# SimonDuino.net
KiCad netlist of a schematic drawn in Altium Designer
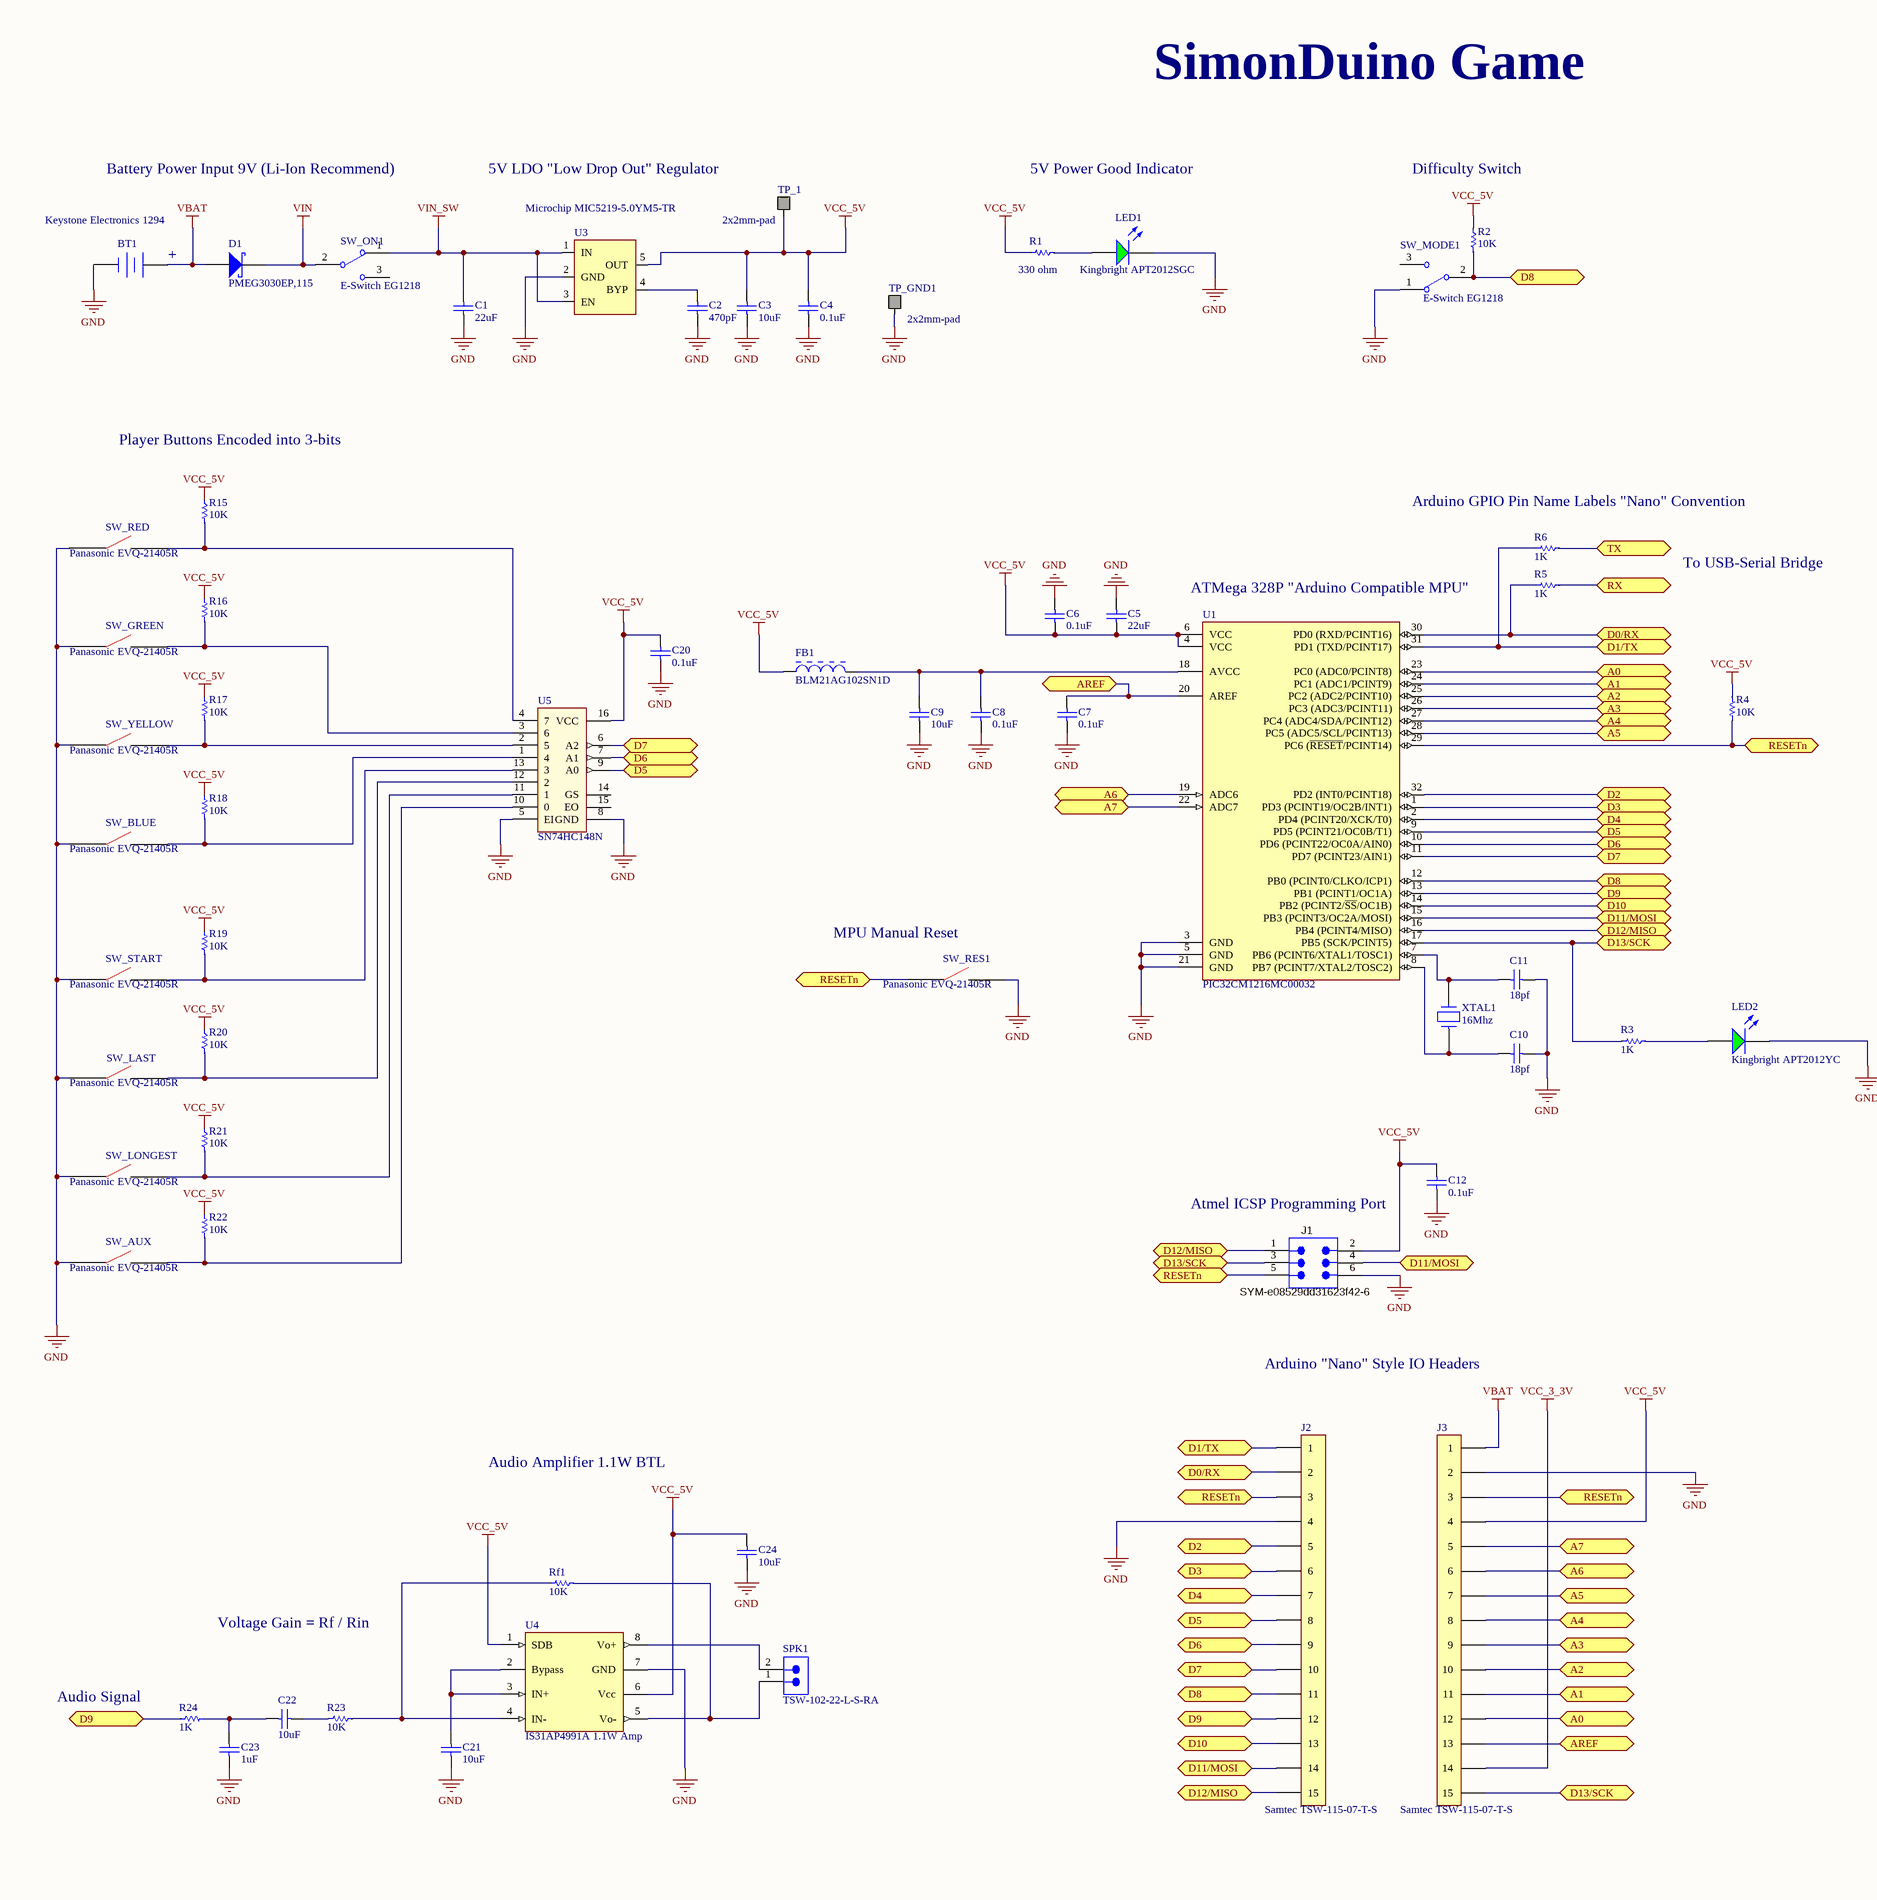
[diagram p0: SimonDuino.SchDoc, left]
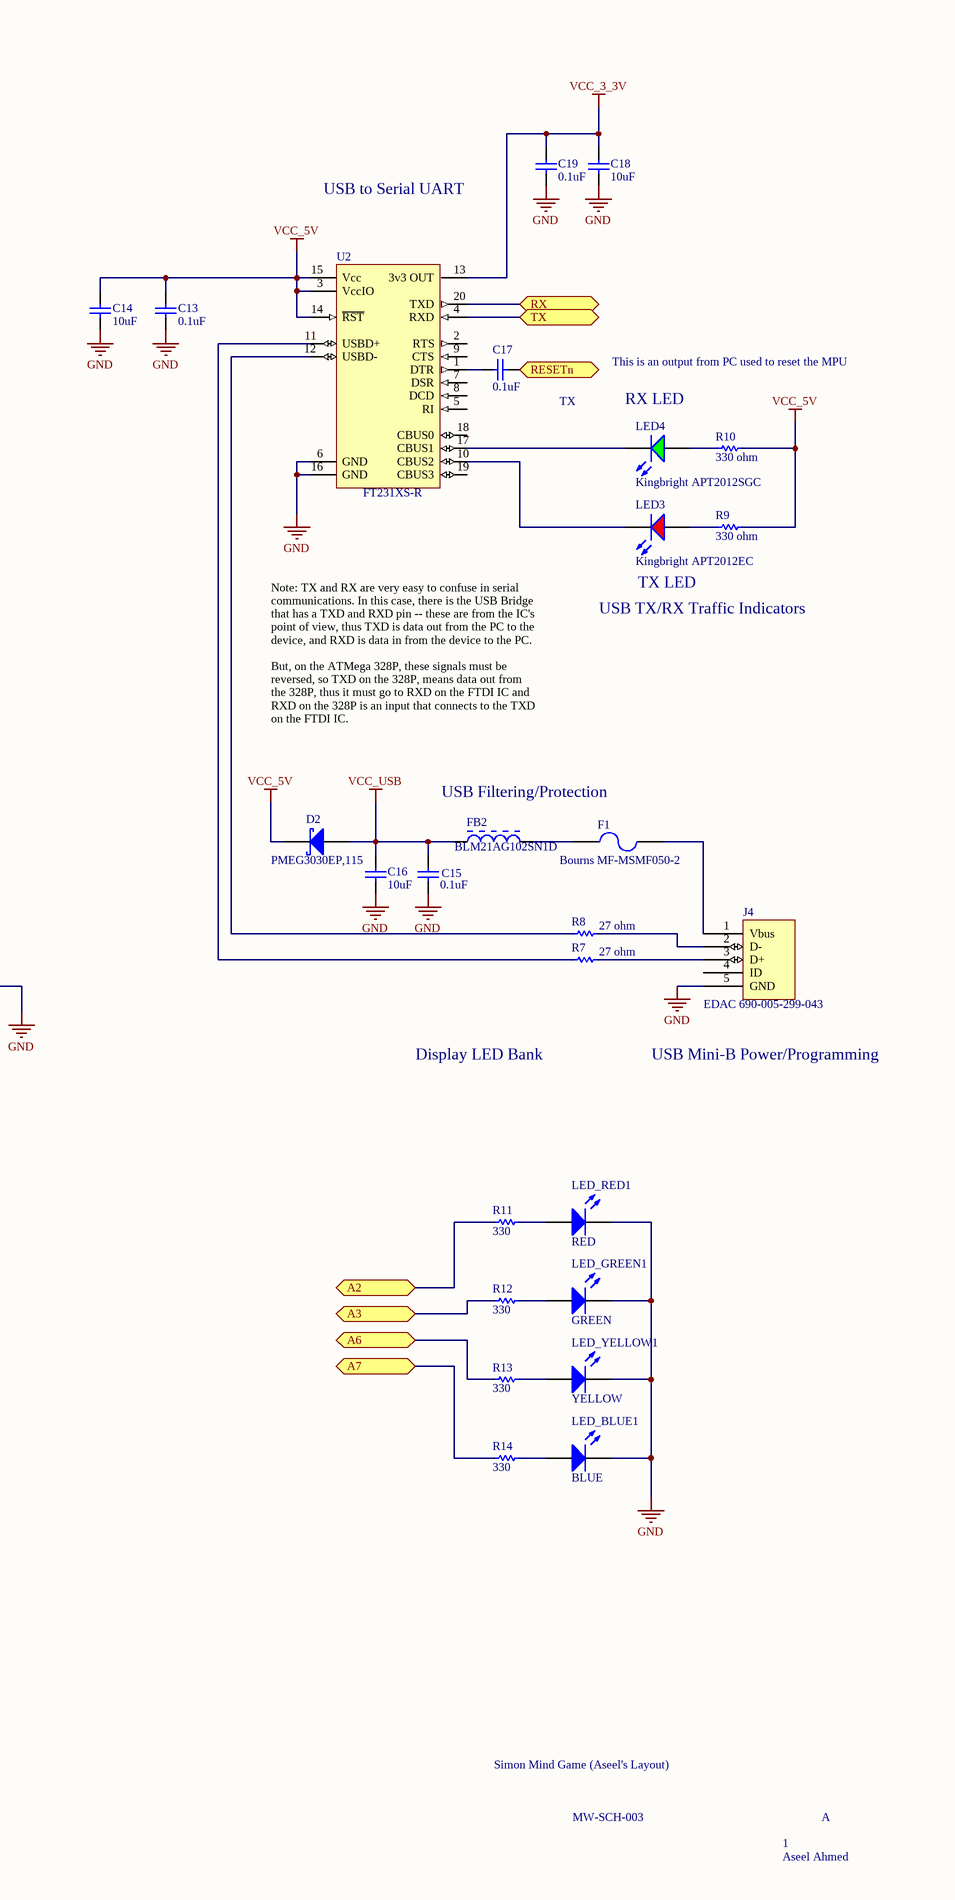
[diagram p1: SimonDuino.SchDoc, right]

(export (version "E")
  (design (tool "Eeschema 10.0.6"))
  (components
    (comp (ref "BT1")
      (value "Keystone Electronics 1294")
      (footprint "PCB-3798-1")
      (description "HOLDER BATT 9V UNIV PLASTIC PC")
      (libsource (lib "Octopart library") (part "SYM-3798-1"))
    )
    (comp (ref "C1")
      (value "22uF")
      (footprint "RLP133A")
      (description "Generic Multilayer Ceramic Capacitor SMD 0805 (2012)")
      (libsource (lib "Octopart library") (part "SYM-3c98f6df3913e35f-5"))
    )
    (comp (ref "C2")
      (value "470pF")
      (footprint "RLP133A")
      (description "Generic Multilayer Ceramic Capacitor SMD 0805 (2012)")
      (libsource (lib "CommunityVault") (part "SYM-3c98f6df3913e35f-5"))
    )
    (comp (ref "C3")
      (value "10uF")
      (footprint "RLP133A")
      (description "Generic Multilayer Ceramic Capacitor SMD 0805 (2012)")
      (libsource (lib "Octopart library") (part "SYM-3c98f6df3913e35f-5"))
    )
    (comp (ref "C4")
      (value "0.1uF")
      (footprint "RLP133A")
      (description "Generic Multilayer Ceramic Capacitor SMD 0805 (2012)")
      (libsource (lib "Octopart library") (part "SYM-3c98f6df3913e35f-5"))
    )
    (comp (ref "C5")
      (value "22uF")
      (footprint "RLP133A")
      (description "Generic Multilayer Ceramic Capacitor SMD 0805 (2012)")
      (libsource (lib "Octopart library") (part "SYM-3c98f6df3913e35f-5"))
    )
    (comp (ref "C6")
      (value "0.1uF")
      (footprint "RLP133A")
      (description "Generic Multilayer Ceramic Capacitor SMD 0805 (2012)")
      (libsource (lib "Octopart library") (part "SYM-3c98f6df3913e35f-5"))
    )
    (comp (ref "C7")
      (value "0.1uF")
      (footprint "RLP133A")
      (description "Generic Multilayer Ceramic Capacitor SMD 0805 (2012)")
      (libsource (lib "Octopart library") (part "SYM-3c98f6df3913e35f-5"))
    )
    (comp (ref "C8")
      (value "0.1uF")
      (footprint "RLP133A")
      (description "Generic Multilayer Ceramic Capacitor SMD 0805 (2012)")
      (libsource (lib "Octopart library") (part "SYM-3c98f6df3913e35f-5"))
    )
    (comp (ref "C9")
      (value "10uF")
      (footprint "RLP133A")
      (description "Generic Multilayer Ceramic Capacitor SMD 0805 (2012)")
      (libsource (lib "Octopart library") (part "SYM-3c98f6df3913e35f-5"))
    )
    (comp (ref "C10")
      (value "18pf")
      (footprint "RLP133A")
      (description "Generic Multilayer Ceramic Capacitor SMD 0805 (2012)")
      (libsource (lib "Octopart library") (part "SYM-3c98f6df3913e35f-5"))
    )
    (comp (ref "C11")
      (value "18pf")
      (footprint "RLP133A")
      (description "Generic Multilayer Ceramic Capacitor SMD 0805 (2012)")
      (libsource (lib "Octopart library") (part "SYM-3c98f6df3913e35f-5"))
    )
    (comp (ref "C12")
      (value "0.1uF")
      (footprint "RLP133A")
      (description "Generic Multilayer Ceramic Capacitor SMD 0805 (2012)")
      (libsource (lib "Octopart library") (part "SYM-3c98f6df3913e35f-5"))
    )
    (comp (ref "C13")
      (value "0.1uF")
      (footprint "RLP133A")
      (description "Generic Multilayer Ceramic Capacitor SMD 0805 (2012)")
      (libsource (lib "Octopart library") (part "SYM-3c98f6df3913e35f-5"))
    )
    (comp (ref "C14")
      (value "10uF")
      (footprint "RLP133A")
      (description "Generic Multilayer Ceramic Capacitor SMD 0805 (2012)")
      (libsource (lib "Octopart library") (part "SYM-3c98f6df3913e35f-5"))
    )
    (comp (ref "C15")
      (value "0.1uF")
      (footprint "RLP133A")
      (description "Generic Multilayer Ceramic Capacitor SMD 0805 (2012)")
      (libsource (lib "Octopart library") (part "SYM-3c98f6df3913e35f-5"))
    )
    (comp (ref "C16")
      (value "10uF")
      (footprint "RLP133A")
      (description "Generic Multilayer Ceramic Capacitor SMD 0805 (2012)")
      (libsource (lib "Octopart library") (part "SYM-3c98f6df3913e35f-5"))
    )
    (comp (ref "C17")
      (value "0.1uF")
      (footprint "RLP133A")
      (description "Generic Multilayer Ceramic Capacitor SMD 0805 (2012)")
      (libsource (lib "Octopart library") (part "SYM-3c98f6df3913e35f-5"))
    )
    (comp (ref "C18")
      (value "10uF")
      (footprint "RLP133A")
      (description "Generic Multilayer Ceramic Capacitor SMD 0805 (2012)")
      (libsource (lib "Octopart library") (part "SYM-3c98f6df3913e35f-5"))
    )
    (comp (ref "C19")
      (value "0.1uF")
      (footprint "RLP133A")
      (description "Generic Multilayer Ceramic Capacitor SMD 0805 (2012)")
      (libsource (lib "Octopart library") (part "SYM-3c98f6df3913e35f-5"))
    )
    (comp (ref "C20")
      (value "0.1uF")
      (footprint "RLP133A")
      (description "Generic Multilayer Ceramic Capacitor SMD 0805 (2012)")
      (libsource (lib "Octopart library") (part "SYM-3c98f6df3913e35f-5"))
    )
    (comp (ref "C21")
      (value "10uF")
      (footprint "RLP133A")
      (description "Generic Multilayer Ceramic Capacitor SMD 0805 (2012)")
      (libsource (lib "Octopart library") (part "SYM-3c98f6df3913e35f-5"))
    )
    (comp (ref "C22")
      (value "10uF")
      (footprint "RLP133A")
      (description "Generic Multilayer Ceramic Capacitor SMD 0805 (2012)")
      (libsource (lib "Octopart library") (part "SYM-3c98f6df3913e35f-5"))
    )
    (comp (ref "C23")
      (value "1uF")
      (footprint "RLP133A")
      (description "Generic Multilayer Ceramic Capacitor SMD 0805 (2012)")
      (libsource (lib "Octopart library") (part "SYM-3c98f6df3913e35f-5"))
    )
    (comp (ref "C24")
      (value "10uF")
      (footprint "RLP133A")
      (description "Generic Multilayer Ceramic Capacitor SMD 0805 (2012)")
      (libsource (lib "Octopart library") (part "SYM-3c98f6df3913e35f-5"))
    )
    (comp (ref "D1")
      (value "PMEG3030EP,115")
      (footprint "PCB-ylvpw7uho1dkst7hexks-1")
      (description "PMEG3030EP 3 A 30 Vrrm SMT MEGA Schottky Barrier Rectifier - SOD-128F")
      (libsource (lib "Octopart library") (part "SYM-93505b4aaf424c97-1"))
    )
    (comp (ref "D2")
      (value "PMEG3030EP,115")
      (footprint "PCB-ylvpw7uho1dkst7hexks-1")
      (description "PMEG3030EP 3 A 30 Vrrm SMT MEGA Schottky Barrier Rectifier - SOD-128F")
      (libsource (lib "Octopart library") (part "SYM-93505b4aaf424c97-1"))
    )
    (comp (ref "F1")
      (value "Bourns MF-MSMF050-2")
      (footprint "L1812")
      (description "PTC RESETTABLE .50A 15V 1812")
      (libsource (lib "Octopart library") (part "BOUR-MF-MSMF050-2"))
    )
    (comp (ref "FB1")
      (value "BLM21AG102SN1D")
      (footprint "MURA-BLM21-H1-CHIP-2_V")
      (libsource (lib "Octopart library") (part "MURA-FB-2"))
    )
    (comp (ref "FB2")
      (value "BLM21AG102SN1D")
      (footprint "MURA-BLM21-H1-CHIP-2_V")
      (libsource (lib "Octopart library") (part "MURA-FB-2"))
    )
    (comp (ref "J1")
      (value "SYM-e08529dd31623f42-6")
      (footprint "PCB-2h1t0rpz2tx2wsc79kkt-1")
      (description "2.54mm (0.1\") Pitch DIL Vertical PC Tail Pin Header, 6.1mm mating pin height, tin, 3+3 contacts")
      (fields (field (name "MANUFACTURER PART NUMBER") "M20-9980346"))
      (libsource (lib "Octopart library") (part "SYM-e08529dd31623f42-6"))
    )
    (comp (ref "J2")
      (value "Samtec TSW-115-07-T-S")
      (footprint "PCB-ss9uik38su1ryg1jck95-1")
      (description "Conn Unshrouded Header HDR 15 POS 2.54mm Solder ST Thru-Hole Automotive Bulk")
      (libsource (lib "") (part "SYM-3393fa9d3e8bec54-1_1"))
    )
    (comp (ref "J3")
      (value "Samtec TSW-115-07-T-S")
      (footprint "PCB-ss9uik38su1ryg1jck95-1")
      (description "Conn Unshrouded Header HDR 15 POS 2.54mm Solder ST Thru-Hole Automotive Bulk")
      (libsource (lib "Octopart library") (part "SYM-3393fa9d3e8bec54-1"))
    )
    (comp (ref "J4")
      (value "EDAC 690-005-299-043")
      (footprint "PCB-0dqtvzwtjwndkeioqta0-1")
      (description "5 Pin Right Angle Surface Mount Mini USB Type B")
      (libsource (lib "CommunityVault") (part "SYM-f10139da97e32ec6-1"))
    )
    (comp (ref "LED1")
      (value "Kingbright APT2012SGC")
      (footprint "CHIPLED_0805_NOOUTLINE")
      (description "LED 2X1.2MM 568NM GN WTR CLR SMD")
      (libsource (lib "Octopart library") (part "LED_GREEN_AC"))
    )
    (comp (ref "LED2")
      (value "Kingbright APT2012YC")
      (footprint "CHIPLED_0805_NOOUTLINE")
      (description "LED 2X1.2MM 568NM GN WTR CLR SMD")
      (libsource (lib "CommunityVault") (part "CMP-1546221-2"))
    )
    (comp (ref "LED3")
      (value "Kingbright APT2012EC")
      (footprint "CHIPLED_0805_NOOUTLINE")
      (description "LED 2X1.2MM 625NM RD WTR CLR SMD")
      (libsource (lib "Octopart library") (part "LED_RED_AC"))
    )
    (comp (ref "LED4")
      (value "Kingbright APT2012SGC")
      (footprint "CHIPLED_0805_NOOUTLINE")
      (description "LED 2X1.2MM 568NM GN WTR CLR SMD")
      (libsource (lib "Octopart library") (part "LED_GREEN_AC"))
    )
    (comp (ref "LED_BLUE1")
      (value "BLUE")
      (footprint "PCB-teu6t62n2bsx7jl1if62-1")
      (description "LED Uni-Color Green 2-Pin T-1 3/4 Bulk")
      (fields
        (field (name "MANUFACTURER PART NUMBER") "C503B-GCN-CY0C0791")
        (field (name "MANUFACTURER") "Cree")
      )
      (libsource (lib "FavoritesLibrary") (part "SYM-92bb5b2eff764d7c-1"))
    )
    (comp (ref "LED_GREEN1")
      (value "GREEN")
      (footprint "PCB-teu6t62n2bsx7jl1if62-1")
      (description "LED Uni-Color Green 2-Pin T-1 3/4 Bulk")
      (fields
        (field (name "MANUFACTURER PART NUMBER") "C503B-GCN-CY0C0791")
        (field (name "MANUFACTURER") "Cree")
      )
      (libsource (lib "FavoritesLibrary") (part "SYM-92bb5b2eff764d7c-1"))
    )
    (comp (ref "LED_RED1")
      (value "RED")
      (footprint "PCB-teu6t62n2bsx7jl1if62-1")
      (description "LED Uni-Color Green 2-Pin T-1 3/4 Bulk")
      (fields
        (field (name "MANUFACTURER PART NUMBER") "C503B-GCN-CY0C0791")
        (field (name "MANUFACTURER") "Cree")
      )
      (libsource (lib "FavoritesLibrary") (part "SYM-92bb5b2eff764d7c-1"))
    )
    (comp (ref "LED_YELLOW1")
      (value "YELLOW")
      (footprint "PCB-teu6t62n2bsx7jl1if62-1")
      (description "LED Uni-Color Green 2-Pin T-1 3/4 Bulk")
      (fields
        (field (name "MANUFACTURER PART NUMBER") "C503B-GCN-CY0C0791")
        (field (name "MANUFACTURER") "Cree")
      )
      (libsource (lib "FavoritesLibrary") (part "SYM-92bb5b2eff764d7c-1"))
    )
    (comp (ref "R1")
      (value "330 ohm")
      (footprint "RESC2013X70X40LL20T20")
      (description "@ RESISTOR,SMT,0805,1K OHM, +/-1%,+-100ppm,THICKFILM(100)")
      (libsource (lib "Octopart library") (part "RES-2"))
    )
    (comp (ref "R2")
      (value "10K")
      (footprint "RESC2013X70X40LL20T20")
      (description "@ RESISTOR,SMT,0805,1K OHM, +/-1%,+-100ppm,THICKFILM(100)")
      (libsource (lib "Octopart library") (part "RES-2"))
    )
    (comp (ref "R3")
      (value "1K")
      (footprint "RESC2013X70X40LL20T20")
      (description "@ RESISTOR,SMT,0805,1K OHM, +/-1%,+-100ppm,THICKFILM(100)")
      (libsource (lib "Octopart library") (part "RES-2"))
    )
    (comp (ref "R4")
      (value "10K")
      (footprint "RESC2013X70X40LL20T20")
      (description "@ RESISTOR,SMT,0805,1K OHM, +/-1%,+-100ppm,THICKFILM(100)")
      (libsource (lib "Octopart library") (part "RES-2"))
    )
    (comp (ref "R5")
      (value "1K")
      (footprint "RESC2013X70X40LL20T20")
      (description "@ RESISTOR,SMT,0805,1K OHM, +/-1%,+-100ppm,THICKFILM(100)")
      (libsource (lib "Octopart library") (part "RES-2"))
    )
    (comp (ref "R6")
      (value "1K")
      (footprint "RESC2013X70X40LL20T20")
      (description "@ RESISTOR,SMT,0805,1K OHM, +/-1%,+-100ppm,THICKFILM(100)")
      (libsource (lib "Octopart library") (part "RES-2"))
    )
    (comp (ref "R7")
      (value "27 ohm")
      (footprint "RESC2013X70X40LL20T20")
      (description "@ RESISTOR,SMT,0805,1K OHM, +/-1%,+-100ppm,THICKFILM(100)")
      (libsource (lib "Octopart library") (part "RES-2"))
    )
    (comp (ref "R8")
      (value "27 ohm")
      (footprint "RESC2013X70X40LL20T20")
      (description "@ RESISTOR,SMT,0805,1K OHM, +/-1%,+-100ppm,THICKFILM(100)")
      (libsource (lib "Octopart library") (part "RES-2"))
    )
    (comp (ref "R9")
      (value "330 ohm")
      (footprint "RESC2013X70X40LL20T20")
      (description "@ RESISTOR,SMT,0805,1K OHM, +/-1%,+-100ppm,THICKFILM(100)")
      (libsource (lib "Octopart library") (part "RES-2"))
    )
    (comp (ref "R10")
      (value "330 ohm")
      (footprint "RESC2013X70X40LL20T20")
      (description "@ RESISTOR,SMT,0805,1K OHM, +/-1%,+-100ppm,THICKFILM(100)")
      (libsource (lib "Octopart library") (part "RES-2"))
    )
    (comp (ref "R11")
      (value "330")
      (footprint "RESC2013X70X40LL20T20")
      (description "@ RESISTOR,SMT,0805,1K OHM, +/-1%,+-100ppm,THICKFILM(100)")
      (libsource (lib "Octopart library") (part "RES-2"))
    )
    (comp (ref "R12")
      (value "330")
      (footprint "RESC2013X70X40LL20T20")
      (description "@ RESISTOR,SMT,0805,1K OHM, +/-1%,+-100ppm,THICKFILM(100)")
      (libsource (lib "Octopart library") (part "RES-2"))
    )
    (comp (ref "R13")
      (value "330")
      (footprint "RESC2013X70X40LL20T20")
      (description "@ RESISTOR,SMT,0805,1K OHM, +/-1%,+-100ppm,THICKFILM(100)")
      (libsource (lib "Octopart library") (part "RES-2"))
    )
    (comp (ref "R14")
      (value "330")
      (footprint "RESC2013X70X40LL20T20")
      (description "@ RESISTOR,SMT,0805,1K OHM, +/-1%,+-100ppm,THICKFILM(100)")
      (libsource (lib "Octopart library") (part "RES-2"))
    )
    (comp (ref "R15")
      (value "10K")
      (footprint "RESC2013X70X40LL20T20")
      (description "@ RESISTOR,SMT,0805,1K OHM, +/-1%,+-100ppm,THICKFILM(100)")
      (libsource (lib "Octopart library") (part "RES-2"))
    )
    (comp (ref "R16")
      (value "10K")
      (footprint "RESC2013X70X40LL20T20")
      (description "@ RESISTOR,SMT,0805,1K OHM, +/-1%,+-100ppm,THICKFILM(100)")
      (libsource (lib "Octopart library") (part "RES-2"))
    )
    (comp (ref "R17")
      (value "10K")
      (footprint "RESC2013X70X40LL20T20")
      (description "@ RESISTOR,SMT,0805,1K OHM, +/-1%,+-100ppm,THICKFILM(100)")
      (libsource (lib "Octopart library") (part "RES-2"))
    )
    (comp (ref "R18")
      (value "10K")
      (footprint "RESC2013X70X40LL20T20")
      (description "@ RESISTOR,SMT,0805,1K OHM, +/-1%,+-100ppm,THICKFILM(100)")
      (libsource (lib "Octopart library") (part "RES-2"))
    )
    (comp (ref "R19")
      (value "10K")
      (footprint "RESC2013X70X40LL20T20")
      (description "@ RESISTOR,SMT,0805,1K OHM, +/-1%,+-100ppm,THICKFILM(100)")
      (libsource (lib "Octopart library") (part "RES-2"))
    )
    (comp (ref "R20")
      (value "10K")
      (footprint "RESC2013X70X40LL20T20")
      (description "@ RESISTOR,SMT,0805,1K OHM, +/-1%,+-100ppm,THICKFILM(100)")
      (libsource (lib "Octopart library") (part "RES-2"))
    )
    (comp (ref "R21")
      (value "10K")
      (footprint "RESC2013X70X40LL20T20")
      (description "@ RESISTOR,SMT,0805,1K OHM, +/-1%,+-100ppm,THICKFILM(100)")
      (libsource (lib "Octopart library") (part "RES-2"))
    )
    (comp (ref "R22")
      (value "10K")
      (footprint "RESC2013X70X40LL20T20")
      (description "@ RESISTOR,SMT,0805,1K OHM, +/-1%,+-100ppm,THICKFILM(100)")
      (libsource (lib "Octopart library") (part "RES-2"))
    )
    (comp (ref "R23")
      (value "10K")
      (footprint "RESC2013X70X40LL20T20")
      (description "@ RESISTOR,SMT,0805,1K OHM, +/-1%,+-100ppm,THICKFILM(100)")
      (libsource (lib "Octopart library") (part "RES-2"))
    )
    (comp (ref "R24")
      (value "1K")
      (footprint "RESC2013X70X40LL20T20")
      (description "@ RESISTOR,SMT,0805,1K OHM, +/-1%,+-100ppm,THICKFILM(100)")
      (libsource (lib "Octopart library") (part "RES-2"))
    )
    (comp (ref "Rf1")
      (value "10K")
      (footprint "RESC2013X70X40LL20T20")
      (description "@ RESISTOR,SMT,0805,1K OHM, +/-1%,+-100ppm,THICKFILM(100)")
      (libsource (lib "Octopart library") (part "RES-2"))
    )
    (comp (ref "SPK1")
      (value "TSW-102-22-L-S-RA")
      (footprint "SMTC-TSW-102-22-X-S-RA")
      (libsource (lib "Octopart library") (part "SMTC-TSW-102-X-X-S-X"))
    )
    (comp (ref "SW_AUX")
      (value "Panasonic EVQ-21405R")
      (footprint "PCB-je10m8m3eogq13l465bo-1")
      (description "Switch Tactile N.O. SPST Round Button PC Pins 0.02A 15VDC 1.3N Thru-Hole Radial T/R")
      (fields
        (field (name "ELEMENT14 PART NO.") "2281982")
        (field (name "MANUFACTURER PART NUMBER") "EVQ-21405R")
      )
      (libsource (lib "FavoritesLibrary") (part "SYM-2fe5e5be239cf022-1"))
    )
    (comp (ref "SW_BLUE")
      (value "Panasonic EVQ-21405R")
      (footprint "PCB-je10m8m3eogq13l465bo-1")
      (description "Switch Tactile N.O. SPST Round Button PC Pins 0.02A 15VDC 1.3N Thru-Hole Radial T/R")
      (fields
        (field (name "ELEMENT14 PART NO.") "2281982")
        (field (name "MANUFACTURER PART NUMBER") "EVQ-21405R")
      )
      (libsource (lib "FavoritesLibrary") (part "SYM-2fe5e5be239cf022-1"))
    )
    (comp (ref "SW_GREEN")
      (value "Panasonic EVQ-21405R")
      (footprint "PCB-je10m8m3eogq13l465bo-1")
      (description "Switch Tactile N.O. SPST Round Button PC Pins 0.02A 15VDC 1.3N Thru-Hole Radial T/R")
      (fields
        (field (name "ELEMENT14 PART NO.") "2281982")
        (field (name "MANUFACTURER PART NUMBER") "EVQ-21405R")
      )
      (libsource (lib "FavoritesLibrary") (part "SYM-2fe5e5be239cf022-1"))
    )
    (comp (ref "SW_LAST")
      (value "Panasonic EVQ-21405R")
      (footprint "PCB-je10m8m3eogq13l465bo-1")
      (description "Switch Tactile N.O. SPST Round Button PC Pins 0.02A 15VDC 1.3N Thru-Hole Radial T/R")
      (fields
        (field (name "ELEMENT14 PART NO.") "2281982")
        (field (name "MANUFACTURER PART NUMBER") "EVQ-21405R")
      )
      (libsource (lib "FavoritesLibrary") (part "SYM-2fe5e5be239cf022-1"))
    )
    (comp (ref "SW_LONGEST")
      (value "Panasonic EVQ-21405R")
      (footprint "PCB-je10m8m3eogq13l465bo-1")
      (description "Switch Tactile N.O. SPST Round Button PC Pins 0.02A 15VDC 1.3N Thru-Hole Radial T/R")
      (fields
        (field (name "ELEMENT14 PART NO.") "2281982")
        (field (name "MANUFACTURER PART NUMBER") "EVQ-21405R")
      )
      (libsource (lib "FavoritesLibrary") (part "SYM-2fe5e5be239cf022-1"))
    )
    (comp (ref "SW_MODE1")
      (value "E-Switch EG1218")
      (footprint "ESWI-EG1218_V")
      (description "Slide Switch, 500 V, -20 to 70 degC, 3-Pin THD, RoHS")
      (fields (field (name "MANUFACTURER PART NUMBER") "EG1218"))
      (libsource (lib "FavoritesLibrary") (part "SW-SPDT-3_B"))
    )
    (comp (ref "SW_ON1")
      (value "E-Switch EG1218")
      (footprint "ESWI-EG1218_V")
      (description "Slide Switch, 500 V, -20 to 70 degC, 3-Pin THD, RoHS")
      (fields (field (name "MANUFACTURER PART NUMBER") "EG1218"))
      (libsource (lib "FavoritesLibrary") (part "SW-SPDT-3_B"))
    )
    (comp (ref "SW_RED")
      (value "Panasonic EVQ-21405R")
      (footprint "PCB-je10m8m3eogq13l465bo-1")
      (description "Switch Tactile N.O. SPST Round Button PC Pins 0.02A 15VDC 1.3N Thru-Hole Radial T/R")
      (fields
        (field (name "ELEMENT14 PART NO.") "2281982")
        (field (name "MANUFACTURER PART NUMBER") "EVQ-21405R")
      )
      (libsource (lib "FavoritesLibrary") (part "SYM-2fe5e5be239cf022-1"))
    )
    (comp (ref "SW_RES1")
      (value "Panasonic EVQ-21405R")
      (footprint "PCB-je10m8m3eogq13l465bo-1")
      (description "Switch Tactile N.O. SPST Round Button PC Pins 0.02A 15VDC 1.3N Thru-Hole Radial T/R")
      (fields
        (field (name "ELEMENT14 PART NO.") "2281982")
        (field (name "MANUFACTURER PART NUMBER") "EVQ-21405R")
      )
      (libsource (lib "FavoritesLibrary") (part "SYM-2fe5e5be239cf022-1"))
    )
    (comp (ref "SW_START")
      (value "Panasonic EVQ-21405R")
      (footprint "PCB-je10m8m3eogq13l465bo-1")
      (description "Switch Tactile N.O. SPST Round Button PC Pins 0.02A 15VDC 1.3N Thru-Hole Radial T/R")
      (fields
        (field (name "ELEMENT14 PART NO.") "2281982")
        (field (name "MANUFACTURER PART NUMBER") "EVQ-21405R")
      )
      (libsource (lib "FavoritesLibrary") (part "SYM-2fe5e5be239cf022-1"))
    )
    (comp (ref "SW_YELLOW")
      (value "Panasonic EVQ-21405R")
      (footprint "PCB-je10m8m3eogq13l465bo-1")
      (description "Switch Tactile N.O. SPST Round Button PC Pins 0.02A 15VDC 1.3N Thru-Hole Radial T/R")
      (fields
        (field (name "ELEMENT14 PART NO.") "2281982")
        (field (name "MANUFACTURER PART NUMBER") "EVQ-21405R")
      )
      (libsource (lib "FavoritesLibrary") (part "SYM-2fe5e5be239cf022-1"))
    )
    (comp (ref "TP_1")
      (value "2x2mm-pad")
      (footprint "PCB-iek5qk9ganu4yn12lo6h-1")
      (description "Raychem; SMT Circuit probe pad, 0805, 0R0 RCT")
      (libsource (lib "Octopart library") (part "SYM-da21135b2be305e6-1"))
    )
    (comp (ref "TP_GND1")
      (value "2x2mm-pad")
      (footprint "PCB-iek5qk9ganu4yn12lo6h-1")
      (description "Raychem; SMT Circuit probe pad, 0805, 0R0 RCT")
      (libsource (lib "Octopart library") (part "SYM-da21135b2be305e6-1"))
    )
    (comp (ref "U1")
      (value "PIC32CM1216MC00032")
      (footprint "Quad32")
      (description "5V Cortex ARM M0+ with 128K Flash and 16K RAM")
      (libsource (lib "My Personal Space") (part "MC-8B-ATM48-SQ32"))
    )
    (comp (ref "U2")
      (value "FT231XS-R")
      (footprint "SSOP20_L")
      (description "USB Full Speed to Full Handshake UART with USB Charger Detection")
      (fields (field (name "MANUFACTURER") "Future Technologies"))
      (libsource (lib "My Personal Space") (part "SYM-1bffd7075986c438-1"))
    )
    (comp (ref "U3")
      (value "Microchip MIC5219-5.0YM5-TR")
      (footprint "PCB-wkjlo8hhy83bmub82728-1")
      (description "MIC5219 Series 500 mA 5 V Fixed Output Surface Mount LDO Regulator - SOT-23-5")
      (fields (field (name "MANUFACTURER PART NUMBER") "MIC5219-5.0YM5-TR"))
      (libsource (lib "CommunityVault") (part "SYM-8be04111fcdb5427-1"))
    )
    (comp (ref "U4")
      (value "IS31AP4991A 1.1W Amp")
      (footprint "PCB-9rmbxp4o58shl47xlmib-1")
      (description "Audio Amp Speaker 1-CH Mono 1.4W Class-AB 8-Pin SOP T/R")
      (libsource (lib "Octopart library") (part "SYM-b3f478ed30436c33-1"))
    )
    (comp (ref "U5")
      (value "SN74HC148N")
      (footprint "PCB-humlfp2qb5uk19pmpc47-1")
      (description "8-Line To 3-Line Priority Encoders 16-SOIC -40 to 85")
      (libsource (lib "Octopart library") (part "SYM-21e6e8edbd0afe21-1"))
    )
    (comp (ref "XTAL1")
      (value "16Mhz")
      (footprint "PCB-tw4o7k9ciwtd4bkcirmp-1")
      (description "Crystal 16.0000 MHz")
      (fields (field (name "MANUFACTURER PART NUMBER") "9B-16.000MEEJ-B"))
      (libsource (lib "Octopart library") (part "SYM-9941515555464686-1"))
    )
  )
  (nets
    (net (code "1") (name "/A0") (class "Default")
      (node (ref "J3") (pin "12") (pinfunction "12_12") (pintype "passive"))
      (node (ref "U1") (pin "23") (pinfunction "PC0_(ADC0/PCINT8)_23") (pintype "bidirectional"))
    )
    (net (code "2") (name "/A1") (class "Default")
      (node (ref "J3") (pin "11") (pinfunction "11_11") (pintype "passive"))
      (node (ref "U1") (pin "24") (pinfunction "PC1_(ADC1/PCINT9)_24") (pintype "bidirectional"))
    )
    (net (code "3") (name "/A2") (class "Default")
      (node (ref "J3") (pin "10") (pinfunction "10_10") (pintype "passive"))
      (node (ref "R11") (pin "1") (pinfunction "1_1") (pintype "passive"))
      (node (ref "U1") (pin "25") (pinfunction "PC2_(ADC2/PCINT10)_25") (pintype "bidirectional"))
    )
    (net (code "4") (name "/A3") (class "Default")
      (node (ref "J3") (pin "9") (pinfunction "9_9") (pintype "passive"))
      (node (ref "R12") (pin "1") (pinfunction "1_1") (pintype "passive"))
      (node (ref "U1") (pin "26") (pinfunction "PC3_(ADC3/PCINT11)_26") (pintype "bidirectional"))
    )
    (net (code "5") (name "/A4") (class "Default")
      (node (ref "J3") (pin "8") (pinfunction "8_8") (pintype "passive"))
      (node (ref "U1") (pin "27") (pinfunction "PC4_(ADC4/SDA/PCINT12)_27") (pintype "bidirectional"))
    )
    (net (code "6") (name "/A5") (class "Default")
      (node (ref "J3") (pin "7") (pinfunction "7_7") (pintype "passive"))
      (node (ref "U1") (pin "28") (pinfunction "PC5_(ADC5/SCL/PCINT13)_28") (pintype "bidirectional"))
    )
    (net (code "7") (name "/A6") (class "Default")
      (node (ref "J3") (pin "6") (pinfunction "6_6") (pintype "passive"))
      (node (ref "R13") (pin "1") (pinfunction "1_1") (pintype "passive"))
      (node (ref "U1") (pin "19") (pinfunction "ADC6_19") (pintype "input"))
    )
    (net (code "8") (name "/A7") (class "Default")
      (node (ref "J3") (pin "5") (pinfunction "5_5") (pintype "passive"))
      (node (ref "R14") (pin "1") (pinfunction "1_1") (pintype "passive"))
      (node (ref "U1") (pin "22") (pinfunction "ADC7_22") (pintype "input"))
    )
    (net (code "9") (name "/AREF") (class "Default")
      (node (ref "C7") (pin "1") (pinfunction "1_1") (pintype "passive"))
      (node (ref "J3") (pin "13") (pinfunction "13_13") (pintype "passive"))
      (node (ref "U1") (pin "20") (pinfunction "AREF_20") (pintype "passive"))
    )
    (net (code "10") (name "/D0{slash}RX") (class "Default")
      (node (ref "J2") (pin "2") (pinfunction "2_2") (pintype "passive"))
      (node (ref "R5") (pin "1") (pinfunction "1_1") (pintype "passive"))
      (node (ref "U1") (pin "30") (pinfunction "PD0_(RXD/PCINT16)_30") (pintype "bidirectional"))
    )
    (net (code "11") (name "/D1{slash}TX") (class "Default")
      (node (ref "J2") (pin "1") (pinfunction "1_1") (pintype "passive"))
      (node (ref "R6") (pin "1") (pinfunction "1_1") (pintype "passive"))
      (node (ref "U1") (pin "31") (pinfunction "PD1_(TXD/PCINT17)_31") (pintype "bidirectional"))
    )
    (net (code "12") (name "/D2") (class "Default")
      (node (ref "J2") (pin "5") (pinfunction "5_5") (pintype "passive"))
      (node (ref "U1") (pin "32") (pinfunction "PD2_(INT0/PCINT18)_32") (pintype "bidirectional"))
    )
    (net (code "13") (name "/D3") (class "Default")
      (node (ref "J2") (pin "6") (pinfunction "6_6") (pintype "passive"))
      (node (ref "U1") (pin "1") (pinfunction "PD3_(PCINT19/OC2B/INT1)_1") (pintype "bidirectional"))
    )
    (net (code "14") (name "/D4") (class "Default")
      (node (ref "J2") (pin "7") (pinfunction "7_7") (pintype "passive"))
      (node (ref "U1") (pin "2") (pinfunction "PD4_(PCINT20/XCK/T0)_2") (pintype "bidirectional"))
    )
    (net (code "15") (name "/D5") (class "Default")
      (node (ref "J2") (pin "8") (pinfunction "8_8") (pintype "passive"))
      (node (ref "U1") (pin "9") (pinfunction "PD5_(PCINT21/OC0B/T1)_9") (pintype "bidirectional"))
      (node (ref "U5") (pin "9") (pinfunction "A0_9") (pintype "output"))
    )
    (net (code "16") (name "/D6") (class "Default")
      (node (ref "J2") (pin "9") (pinfunction "9_9") (pintype "passive"))
      (node (ref "U1") (pin "10") (pinfunction "PD6_(PCINT22/OC0A/AIN0)_10") (pintype "bidirectional"))
      (node (ref "U5") (pin "7") (pinfunction "A1_7") (pintype "output"))
    )
    (net (code "17") (name "/D7") (class "Default")
      (node (ref "J2") (pin "10") (pinfunction "10_10") (pintype "passive"))
      (node (ref "U1") (pin "11") (pinfunction "PD7_(PCINT23/AIN1)_11") (pintype "bidirectional"))
      (node (ref "U5") (pin "6") (pinfunction "A2_6") (pintype "output"))
    )
    (net (code "18") (name "/D8") (class "Default")
      (node (ref "J2") (pin "11") (pinfunction "11_11") (pintype "passive"))
      (node (ref "R2") (pin "2") (pinfunction "2_2") (pintype "passive"))
      (node (ref "SW_MODE1") (pin "2") (pinfunction "COM_2") (pintype "passive"))
      (node (ref "U1") (pin "12") (pinfunction "PB0_(PCINT0/CLKO/ICP1)_12") (pintype "bidirectional"))
    )
    (net (code "19") (name "/D9") (class "Default")
      (node (ref "J2") (pin "12") (pinfunction "12_12") (pintype "passive"))
      (node (ref "R24") (pin "2") (pinfunction "2_2") (pintype "passive"))
      (node (ref "U1") (pin "13") (pinfunction "PB1_(PCINT1/OC1A)_13") (pintype "bidirectional"))
    )
    (net (code "20") (name "/D10") (class "Default")
      (node (ref "J2") (pin "13") (pinfunction "13_13") (pintype "passive"))
      (node (ref "U1") (pin "14") (pinfunction "PB2_(PCINT2/~{SS}/OC1B)_14") (pintype "bidirectional"))
    )
    (net (code "21") (name "/D11{slash}MOSI") (class "Default")
      (node (ref "J1") (pin "4") (pinfunction "4_4") (pintype "passive"))
      (node (ref "J2") (pin "14") (pinfunction "14_14") (pintype "passive"))
      (node (ref "U1") (pin "15") (pinfunction "PB3_(PCINT3/OC2A/MOSI)_15") (pintype "bidirectional"))
    )
    (net (code "22") (name "/D12{slash}MISO") (class "Default")
      (node (ref "J1") (pin "1") (pinfunction "1_1") (pintype "passive"))
      (node (ref "J2") (pin "15") (pinfunction "15_15") (pintype "passive"))
      (node (ref "U1") (pin "16") (pinfunction "PB4_(PCINT4/MISO)_16") (pintype "bidirectional"))
    )
    (net (code "23") (name "/D13{slash}SCK") (class "Default")
      (node (ref "J1") (pin "3") (pinfunction "3_3") (pintype "passive"))
      (node (ref "J3") (pin "15") (pinfunction "15_15") (pintype "passive"))
      (node (ref "R3") (pin "1") (pinfunction "1_1") (pintype "passive"))
      (node (ref "U1") (pin "17") (pinfunction "PB5_(SCK/PCINT5)_17") (pintype "bidirectional"))
    )
    (net (code "24") (name "/RESETn") (class "Default")
      (node (ref "C17") (pin "1") (pinfunction "1_1") (pintype "passive"))
      (node (ref "J1") (pin "5") (pinfunction "5_5") (pintype "passive"))
      (node (ref "J2") (pin "3") (pinfunction "3_3") (pintype "passive"))
      (node (ref "J3") (pin "3") (pinfunction "3_3") (pintype "passive"))
      (node (ref "R4") (pin "1") (pinfunction "1_1") (pintype "passive"))
      (node (ref "SW_RES1") (pin "1") (pinfunction "1_1") (pintype "passive"))
      (node (ref "U1") (pin "29") (pinfunction "PC6_(~{RESET}/PCINT14)_29") (pintype "bidirectional"))
    )
    (net (code "25") (name "/RX") (class "Default")
      (node (ref "R5") (pin "2") (pinfunction "2_2") (pintype "passive"))
      (node (ref "U2") (pin "20") (pinfunction "TXD_20") (pintype "output"))
    )
    (net (code "26") (name "/TX") (class "Default")
      (node (ref "R6") (pin "2") (pinfunction "2_2") (pintype "passive"))
      (node (ref "U2") (pin "4") (pinfunction "RXD_4") (pintype "input"))
    )
    (net (code "27") (name "GND") (class "Default")
      (node (ref "BT1") (pin "2") (pinfunction "-_2") (pintype "passive"))
      (node (ref "C1") (pin "1") (pinfunction "1_1") (pintype "passive"))
      (node (ref "C10") (pin "1") (pinfunction "1_1") (pintype "passive"))
      (node (ref "C11") (pin "1") (pinfunction "1_1") (pintype "passive"))
      (node (ref "C12") (pin "2") (pinfunction "2_2") (pintype "passive"))
      (node (ref "C13") (pin "1") (pinfunction "1_1") (pintype "passive"))
      (node (ref "C14") (pin "1") (pinfunction "1_1") (pintype "passive"))
      (node (ref "C15") (pin "1") (pinfunction "1_1") (pintype "passive"))
      (node (ref "C16") (pin "1") (pinfunction "1_1") (pintype "passive"))
      (node (ref "C18") (pin "1") (pinfunction "1_1") (pintype "passive"))
      (node (ref "C19") (pin "1") (pinfunction "1_1") (pintype "passive"))
      (node (ref "C2") (pin "1") (pinfunction "1_1") (pintype "passive"))
      (node (ref "C20") (pin "1") (pinfunction "1_1") (pintype "passive"))
      (node (ref "C21") (pin "1") (pinfunction "1_1") (pintype "passive"))
      (node (ref "C23") (pin "2") (pinfunction "2_2") (pintype "passive"))
      (node (ref "C24") (pin "1") (pinfunction "1_1") (pintype "passive"))
      (node (ref "C3") (pin "1") (pinfunction "1_1") (pintype "passive"))
      (node (ref "C4") (pin "1") (pinfunction "1_1") (pintype "passive"))
      (node (ref "C5") (pin "1") (pinfunction "1_1") (pintype "passive"))
      (node (ref "C6") (pin "1") (pinfunction "1_1") (pintype "passive"))
      (node (ref "C7") (pin "2") (pinfunction "2_2") (pintype "passive"))
      (node (ref "C8") (pin "1") (pinfunction "1_1") (pintype "passive"))
      (node (ref "C9") (pin "1") (pinfunction "1_1") (pintype "passive"))
      (node (ref "J1") (pin "6") (pinfunction "6_6") (pintype "passive"))
      (node (ref "J2") (pin "4") (pinfunction "4_4") (pintype "passive"))
      (node (ref "J3") (pin "2") (pinfunction "2_2") (pintype "passive"))
      (node (ref "J4") (pin "5") (pinfunction "GND_5") (pintype "power_in"))
      (node (ref "LED1") (pin "C") (pinfunction "C_C") (pintype "passive"))
      (node (ref "LED2") (pin "C") (pinfunction "C_C") (pintype "passive"))
      (node (ref "LED_BLUE1") (pin "1") (pinfunction "K_1") (pintype "passive"))
      (node (ref "LED_GREEN1") (pin "1") (pinfunction "K_1") (pintype "passive"))
      (node (ref "LED_RED1") (pin "1") (pinfunction "K_1") (pintype "passive"))
      (node (ref "LED_YELLOW1") (pin "1") (pinfunction "K_1") (pintype "passive"))
      (node (ref "SW_AUX") (pin "1") (pinfunction "1_1") (pintype "passive"))
      (node (ref "SW_BLUE") (pin "1") (pinfunction "1_1") (pintype "passive"))
      (node (ref "SW_GREEN") (pin "1") (pinfunction "1_1") (pintype "passive"))
      (node (ref "SW_LAST") (pin "1") (pinfunction "1_1") (pintype "passive"))
      (node (ref "SW_LONGEST") (pin "1") (pinfunction "1_1") (pintype "passive"))
      (node (ref "SW_MODE1") (pin "1") (pinfunction "1_1") (pintype "passive"))
      (node (ref "SW_RED") (pin "1") (pinfunction "1_1") (pintype "passive"))
      (node (ref "SW_RES1") (pin "2") (pinfunction "2_2") (pintype "passive"))
      (node (ref "SW_START") (pin "1") (pinfunction "1_1") (pintype "passive"))
      (node (ref "SW_YELLOW") (pin "1") (pinfunction "1_1") (pintype "passive"))
      (node (ref "TP_GND1") (pin "1") (pinfunction "1_1") (pintype "passive"))
      (node (ref "U1") (pin "21") (pinfunction "GND_21") (pintype "power_in"))
      (node (ref "U1") (pin "3") (pinfunction "GND_3") (pintype "power_in"))
      (node (ref "U1") (pin "5") (pinfunction "GND_5") (pintype "power_in"))
      (node (ref "U2") (pin "16") (pinfunction "GND_16") (pintype "power_in"))
      (node (ref "U2") (pin "6") (pinfunction "GND_6") (pintype "power_in"))
      (node (ref "U3") (pin "2") (pinfunction "GND_2") (pintype "passive"))
      (node (ref "U4") (pin "7") (pinfunction "GND_7") (pintype "power_in"))
      (node (ref "U5") (pin "5") (pinfunction "EI_5") (pintype "passive"))
      (node (ref "U5") (pin "8") (pinfunction "GND_8") (pintype "power_in"))
    )
    (net (code "28") (name "Net-(C22-Pad1)") (class "Default")
      (node (ref "C22") (pin "1") (pinfunction "1_1") (pintype "passive"))
      (node (ref "R23") (pin "1") (pinfunction "1_1") (pintype "passive"))
    )
    (net (code "29") (name "Net-(C22-Pad2)") (class "Default")
      (node (ref "C22") (pin "2") (pinfunction "2_2") (pintype "passive"))
      (node (ref "C23") (pin "1") (pinfunction "1_1") (pintype "passive"))
      (node (ref "R24") (pin "1") (pinfunction "1_1") (pintype "passive"))
    )
    (net (code "30") (name "Net-(F1-Pad1)") (class "Default")
      (node (ref "F1") (pin "1") (pinfunction "1_1") (pintype "passive"))
      (node (ref "FB2") (pin "2") (pinfunction "2_2") (pintype "passive"))
    )
    (net (code "31") (name "Net-(J4-D+)") (class "Default")
      (node (ref "J4") (pin "3") (pinfunction "D+_3") (pintype "bidirectional"))
      (node (ref "R7") (pin "2") (pinfunction "2_2") (pintype "passive"))
    )
    (net (code "32") (name "Net-(J4-D-)") (class "Default")
      (node (ref "J4") (pin "2") (pinfunction "D-_2") (pintype "bidirectional"))
      (node (ref "R8") (pin "2") (pinfunction "2_2") (pintype "passive"))
    )
    (net (code "33") (name "Net-(J4-Vbus)") (class "Default")
      (node (ref "F1") (pin "2") (pinfunction "2_2") (pintype "passive"))
      (node (ref "J4") (pin "1") (pinfunction "Vbus_1") (pintype "power_in"))
    )
    (net (code "34") (name "Net-(LED1-PadA)") (class "Default")
      (node (ref "LED1") (pin "A") (pinfunction "A_A") (pintype "passive"))
      (node (ref "R1") (pin "2") (pinfunction "2_2") (pintype "passive"))
    )
    (net (code "35") (name "Net-(LED2-PadA)") (class "Default")
      (node (ref "LED2") (pin "A") (pinfunction "A_A") (pintype "passive"))
      (node (ref "R3") (pin "2") (pinfunction "2_2") (pintype "passive"))
    )
    (net (code "36") (name "Net-(LED3-PadA)") (class "Default")
      (node (ref "LED3") (pin "A") (pinfunction "A_A") (pintype "passive"))
      (node (ref "R9") (pin "2") (pinfunction "2_2") (pintype "passive"))
    )
    (net (code "37") (name "Net-(LED4-PadA)") (class "Default")
      (node (ref "LED4") (pin "A") (pinfunction "A_A") (pintype "passive"))
      (node (ref "R10") (pin "2") (pinfunction "2_2") (pintype "passive"))
    )
    (net (code "38") (name "Net-(LED_BLUE1-A)") (class "Default")
      (node (ref "LED_BLUE1") (pin "2") (pinfunction "A_2") (pintype "passive"))
      (node (ref "R14") (pin "2") (pinfunction "2_2") (pintype "passive"))
    )
    (net (code "39") (name "Net-(LED_GREEN1-A)") (class "Default")
      (node (ref "LED_GREEN1") (pin "2") (pinfunction "A_2") (pintype "passive"))
      (node (ref "R12") (pin "2") (pinfunction "2_2") (pintype "passive"))
    )
    (net (code "40") (name "Net-(LED_RED1-A)") (class "Default")
      (node (ref "LED_RED1") (pin "2") (pinfunction "A_2") (pintype "passive"))
      (node (ref "R11") (pin "2") (pinfunction "2_2") (pintype "passive"))
    )
    (net (code "41") (name "Net-(LED_YELLOW1-A)") (class "Default")
      (node (ref "LED_YELLOW1") (pin "2") (pinfunction "A_2") (pintype "passive"))
      (node (ref "R13") (pin "2") (pinfunction "2_2") (pintype "passive"))
    )
    (net (code "42") (name "Net-(U1-AVCC)") (class "Default")
      (node (ref "C8") (pin "2") (pinfunction "2_2") (pintype "passive"))
      (node (ref "C9") (pin "2") (pinfunction "2_2") (pintype "passive"))
      (node (ref "FB1") (pin "2") (pinfunction "2_2") (pintype "passive"))
      (node (ref "U1") (pin "18") (pinfunction "AVCC_18") (pintype "power_in"))
    )
    (net (code "43") (name "Net-(U1-PB6_(PCINT6{slash}XTAL1{slash}TOSC1))") (class "Default")
      (node (ref "C11") (pin "2") (pinfunction "2_2") (pintype "passive"))
      (node (ref "U1") (pin "7") (pinfunction "PB6_(PCINT6/XTAL1/TOSC1)_7") (pintype "bidirectional"))
      (node (ref "XTAL1") (pin "2") (pinfunction "2_2") (pintype "passive"))
    )
    (net (code "44") (name "Net-(U1-PB7_(PCINT7{slash}XTAL2{slash}TOSC2))") (class "Default")
      (node (ref "C10") (pin "2") (pinfunction "2_2") (pintype "passive"))
      (node (ref "U1") (pin "8") (pinfunction "PB7_(PCINT7/XTAL2/TOSC2)_8") (pintype "bidirectional"))
      (node (ref "XTAL1") (pin "1") (pinfunction "1_1") (pintype "passive"))
    )
    (net (code "45") (name "Net-(U2-CBUS1)") (class "Default")
      (node (ref "LED4") (pin "C") (pinfunction "C_C") (pintype "passive"))
      (node (ref "U2") (pin "17") (pinfunction "CBUS1_17") (pintype "bidirectional"))
    )
    (net (code "46") (name "Net-(U2-CBUS2)") (class "Default")
      (node (ref "LED3") (pin "C") (pinfunction "C_C") (pintype "passive"))
      (node (ref "U2") (pin "10") (pinfunction "CBUS2_10") (pintype "bidirectional"))
    )
    (net (code "47") (name "Net-(U2-DTR)") (class "Default")
      (node (ref "C17") (pin "2") (pinfunction "2_2") (pintype "passive"))
      (node (ref "U2") (pin "1") (pinfunction "DTR_1") (pintype "output"))
    )
    (net (code "48") (name "Net-(U2-USBD+)") (class "Default")
      (node (ref "R7") (pin "1") (pinfunction "1_1") (pintype "passive"))
      (node (ref "U2") (pin "11") (pinfunction "USBD+_11") (pintype "bidirectional"))
    )
    (net (code "49") (name "Net-(U2-USBD-)") (class "Default")
      (node (ref "R8") (pin "1") (pinfunction "1_1") (pintype "passive"))
      (node (ref "U2") (pin "12") (pinfunction "USBD-_12") (pintype "bidirectional"))
    )
    (net (code "50") (name "Net-(U3-BYP)") (class "Default")
      (node (ref "C2") (pin "2") (pinfunction "2_2") (pintype "passive"))
      (node (ref "U3") (pin "4") (pinfunction "BYP_4") (pintype "passive"))
    )
    (net (code "51") (name "Net-(U4-Bypass)") (class "Default")
      (node (ref "C21") (pin "2") (pinfunction "2_2") (pintype "passive"))
      (node (ref "U4") (pin "2") (pinfunction "Bypass_2") (pintype "passive"))
      (node (ref "U4") (pin "3") (pinfunction "IN+_3") (pintype "input"))
    )
    (net (code "52") (name "Net-(U4-IN-)") (class "Default")
      (node (ref "R23") (pin "2") (pinfunction "2_2") (pintype "passive"))
      (node (ref "Rf1") (pin "1") (pinfunction "1_1") (pintype "passive"))
      (node (ref "U4") (pin "4") (pinfunction "IN-_4") (pintype "input"))
    )
    (net (code "53") (name "Net-(U4-Vo+)") (class "Default")
      (node (ref "SPK1") (pin "2") (pinfunction "2_2") (pintype "passive"))
      (node (ref "U4") (pin "8") (pinfunction "Vo+_8") (pintype "output"))
    )
    (net (code "54") (name "Net-(U4-Vo-)") (class "Default")
      (node (ref "Rf1") (pin "2") (pinfunction "2_2") (pintype "passive"))
      (node (ref "SPK1") (pin "1") (pinfunction "1_1") (pintype "passive"))
      (node (ref "U4") (pin "5") (pinfunction "Vo-_5") (pintype "output"))
    )
    (net (code "55") (name "Net-(U5-0)") (class "Default")
      (node (ref "R22") (pin "2") (pinfunction "2_2") (pintype "passive"))
      (node (ref "SW_AUX") (pin "2") (pinfunction "2_2") (pintype "passive"))
      (node (ref "U5") (pin "10") (pinfunction "0_10") (pintype "passive"))
    )
    (net (code "56") (name "Net-(U5-1)") (class "Default")
      (node (ref "R21") (pin "2") (pinfunction "2_2") (pintype "passive"))
      (node (ref "SW_LONGEST") (pin "2") (pinfunction "2_2") (pintype "passive"))
      (node (ref "U5") (pin "11") (pinfunction "1_11") (pintype "passive"))
    )
    (net (code "57") (name "Net-(U5-2)") (class "Default")
      (node (ref "R20") (pin "2") (pinfunction "2_2") (pintype "passive"))
      (node (ref "SW_LAST") (pin "2") (pinfunction "2_2") (pintype "passive"))
      (node (ref "U5") (pin "12") (pinfunction "2_12") (pintype "passive"))
    )
    (net (code "58") (name "Net-(U5-3)") (class "Default")
      (node (ref "R19") (pin "2") (pinfunction "2_2") (pintype "passive"))
      (node (ref "SW_START") (pin "2") (pinfunction "2_2") (pintype "passive"))
      (node (ref "U5") (pin "13") (pinfunction "3_13") (pintype "passive"))
    )
    (net (code "59") (name "Net-(U5-4)") (class "Default")
      (node (ref "R18") (pin "2") (pinfunction "2_2") (pintype "passive"))
      (node (ref "SW_BLUE") (pin "2") (pinfunction "2_2") (pintype "passive"))
      (node (ref "U5") (pin "1") (pinfunction "4_1") (pintype "passive"))
    )
    (net (code "60") (name "Net-(U5-5)") (class "Default")
      (node (ref "R17") (pin "2") (pinfunction "2_2") (pintype "passive"))
      (node (ref "SW_YELLOW") (pin "2") (pinfunction "2_2") (pintype "passive"))
      (node (ref "U5") (pin "2") (pinfunction "5_2") (pintype "passive"))
    )
    (net (code "61") (name "Net-(U5-6)") (class "Default")
      (node (ref "R16") (pin "2") (pinfunction "2_2") (pintype "passive"))
      (node (ref "SW_GREEN") (pin "2") (pinfunction "2_2") (pintype "passive"))
      (node (ref "U5") (pin "3") (pinfunction "6_3") (pintype "passive"))
    )
    (net (code "62") (name "Net-(U5-7)") (class "Default")
      (node (ref "R15") (pin "2") (pinfunction "2_2") (pintype "passive"))
      (node (ref "SW_RED") (pin "2") (pinfunction "2_2") (pintype "passive"))
      (node (ref "U5") (pin "4") (pinfunction "7_4") (pintype "passive"))
    )
    (net (code "63") (name "VBAT") (class "Default")
      (node (ref "BT1") (pin "1") (pinfunction "+_1") (pintype "passive"))
      (node (ref "D1") (pin "1") (pinfunction "A_1") (pintype "passive"))
      (node (ref "J3") (pin "1") (pinfunction "1_1") (pintype "passive"))
    )
    (net (code "64") (name "VCC_3_3V") (class "Default")
      (node (ref "C18") (pin "2") (pinfunction "2_2") (pintype "passive"))
      (node (ref "C19") (pin "2") (pinfunction "2_2") (pintype "passive"))
      (node (ref "J3") (pin "14") (pinfunction "14_14") (pintype "passive"))
      (node (ref "U2") (pin "13") (pinfunction "3v3_OUT_13") (pintype "power_in"))
    )
    (net (code "65") (name "VCC_5V") (class "Default")
      (node (ref "C12") (pin "1") (pinfunction "1_1") (pintype "passive"))
      (node (ref "C13") (pin "2") (pinfunction "2_2") (pintype "passive"))
      (node (ref "C14") (pin "2") (pinfunction "2_2") (pintype "passive"))
      (node (ref "C20") (pin "2") (pinfunction "2_2") (pintype "passive"))
      (node (ref "C24") (pin "2") (pinfunction "2_2") (pintype "passive"))
      (node (ref "C3") (pin "2") (pinfunction "2_2") (pintype "passive"))
      (node (ref "C4") (pin "2") (pinfunction "2_2") (pintype "passive"))
      (node (ref "C5") (pin "2") (pinfunction "2_2") (pintype "passive"))
      (node (ref "C6") (pin "2") (pinfunction "2_2") (pintype "passive"))
      (node (ref "D2") (pin "2") (pinfunction "K_2") (pintype "passive"))
      (node (ref "FB1") (pin "1") (pinfunction "1_1") (pintype "passive"))
      (node (ref "J1") (pin "2") (pinfunction "2_2") (pintype "passive"))
      (node (ref "J3") (pin "4") (pinfunction "4_4") (pintype "passive"))
      (node (ref "R1") (pin "1") (pinfunction "1_1") (pintype "passive"))
      (node (ref "R10") (pin "1") (pinfunction "1_1") (pintype "passive"))
      (node (ref "R15") (pin "1") (pinfunction "1_1") (pintype "passive"))
      (node (ref "R16") (pin "1") (pinfunction "1_1") (pintype "passive"))
      (node (ref "R17") (pin "1") (pinfunction "1_1") (pintype "passive"))
      (node (ref "R18") (pin "1") (pinfunction "1_1") (pintype "passive"))
      (node (ref "R19") (pin "1") (pinfunction "1_1") (pintype "passive"))
      (node (ref "R2") (pin "1") (pinfunction "1_1") (pintype "passive"))
      (node (ref "R20") (pin "1") (pinfunction "1_1") (pintype "passive"))
      (node (ref "R21") (pin "1") (pinfunction "1_1") (pintype "passive"))
      (node (ref "R22") (pin "1") (pinfunction "1_1") (pintype "passive"))
      (node (ref "R4") (pin "2") (pinfunction "2_2") (pintype "passive"))
      (node (ref "R9") (pin "1") (pinfunction "1_1") (pintype "passive"))
      (node (ref "TP_1") (pin "1") (pinfunction "1_1") (pintype "passive"))
      (node (ref "U1") (pin "4") (pinfunction "VCC_4") (pintype "power_in"))
      (node (ref "U1") (pin "6") (pinfunction "VCC_6") (pintype "power_in"))
      (node (ref "U2") (pin "14") (pinfunction "~{RST}_14") (pintype "input"))
      (node (ref "U2") (pin "15") (pinfunction "Vcc_15") (pintype "power_in"))
      (node (ref "U2") (pin "3") (pinfunction "VccIO_3") (pintype "power_in"))
      (node (ref "U3") (pin "5") (pinfunction "OUT_5") (pintype "passive"))
      (node (ref "U4") (pin "1") (pinfunction "SDB_1") (pintype "input"))
      (node (ref "U4") (pin "6") (pinfunction "Vcc_6") (pintype "power_in"))
      (node (ref "U5") (pin "16") (pinfunction "VCC_16") (pintype "power_in"))
    )
    (net (code "66") (name "VCC_USB") (class "Default")
      (node (ref "C15") (pin "2") (pinfunction "2_2") (pintype "passive"))
      (node (ref "C16") (pin "2") (pinfunction "2_2") (pintype "passive"))
      (node (ref "D2") (pin "1") (pinfunction "A_1") (pintype "passive"))
      (node (ref "FB2") (pin "1") (pinfunction "1_1") (pintype "passive"))
    )
    (net (code "67") (name "VIN") (class "Default")
      (node (ref "D1") (pin "2") (pinfunction "K_2") (pintype "passive"))
      (node (ref "SW_ON1") (pin "2") (pinfunction "COM_2") (pintype "passive"))
    )
    (net (code "68") (name "VIN_SW") (class "Default")
      (node (ref "C1") (pin "2") (pinfunction "2_2") (pintype "passive"))
      (node (ref "SW_ON1") (pin "1") (pinfunction "1_1") (pintype "passive"))
      (node (ref "U3") (pin "1") (pinfunction "IN_1") (pintype "passive"))
      (node (ref "U3") (pin "3") (pinfunction "EN_3") (pintype "passive"))
    )
    (net (code "69") (name "unconnected-(J4-ID-Pad4)") (class "Default")
      (node (ref "J4") (pin "4") (pinfunction "ID_4") (pintype "passive"))
    )
    (net (code "70") (name "unconnected-(SW_MODE1-Pad3)") (class "Default")
      (node (ref "SW_MODE1") (pin "3") (pinfunction "3_3") (pintype "passive"))
    )
    (net (code "71") (name "unconnected-(SW_ON1-Pad3)") (class "Default")
      (node (ref "SW_ON1") (pin "3") (pinfunction "3_3") (pintype "passive"))
    )
    (net (code "72") (name "unconnected-(U2-CBUS0-Pad18)") (class "Default")
      (node (ref "U2") (pin "18") (pinfunction "CBUS0_18") (pintype "bidirectional"))
    )
    (net (code "73") (name "unconnected-(U2-CBUS3-Pad19)") (class "Default")
      (node (ref "U2") (pin "19") (pinfunction "CBUS3_19") (pintype "bidirectional"))
    )
    (net (code "74") (name "unconnected-(U2-CTS-Pad9)") (class "Default")
      (node (ref "U2") (pin "9") (pinfunction "CTS_9") (pintype "input"))
    )
    (net (code "75") (name "unconnected-(U2-DCD-Pad8)") (class "Default")
      (node (ref "U2") (pin "8") (pinfunction "DCD_8") (pintype "input"))
    )
    (net (code "76") (name "unconnected-(U2-DSR-Pad7)") (class "Default")
      (node (ref "U2") (pin "7") (pinfunction "DSR_7") (pintype "input"))
    )
    (net (code "77") (name "unconnected-(U2-RI-Pad5)") (class "Default")
      (node (ref "U2") (pin "5") (pinfunction "RI_5") (pintype "input"))
    )
    (net (code "78") (name "unconnected-(U2-RTS-Pad2)") (class "Default")
      (node (ref "U2") (pin "2") (pinfunction "RTS_2") (pintype "output"))
    )
    (net (code "79") (name "unconnected-(U5-EO-Pad15)") (class "Default")
      (node (ref "U5") (pin "15") (pinfunction "EO_15") (pintype "passive"))
    )
    (net (code "80") (name "unconnected-(U5-GS-Pad14)") (class "Default")
      (node (ref "U5") (pin "14") (pinfunction "GS_14") (pintype "passive"))
    )
  )
)
